# eGatewayShield.net
KiCad netlist of a schematic drawn in EAGLE
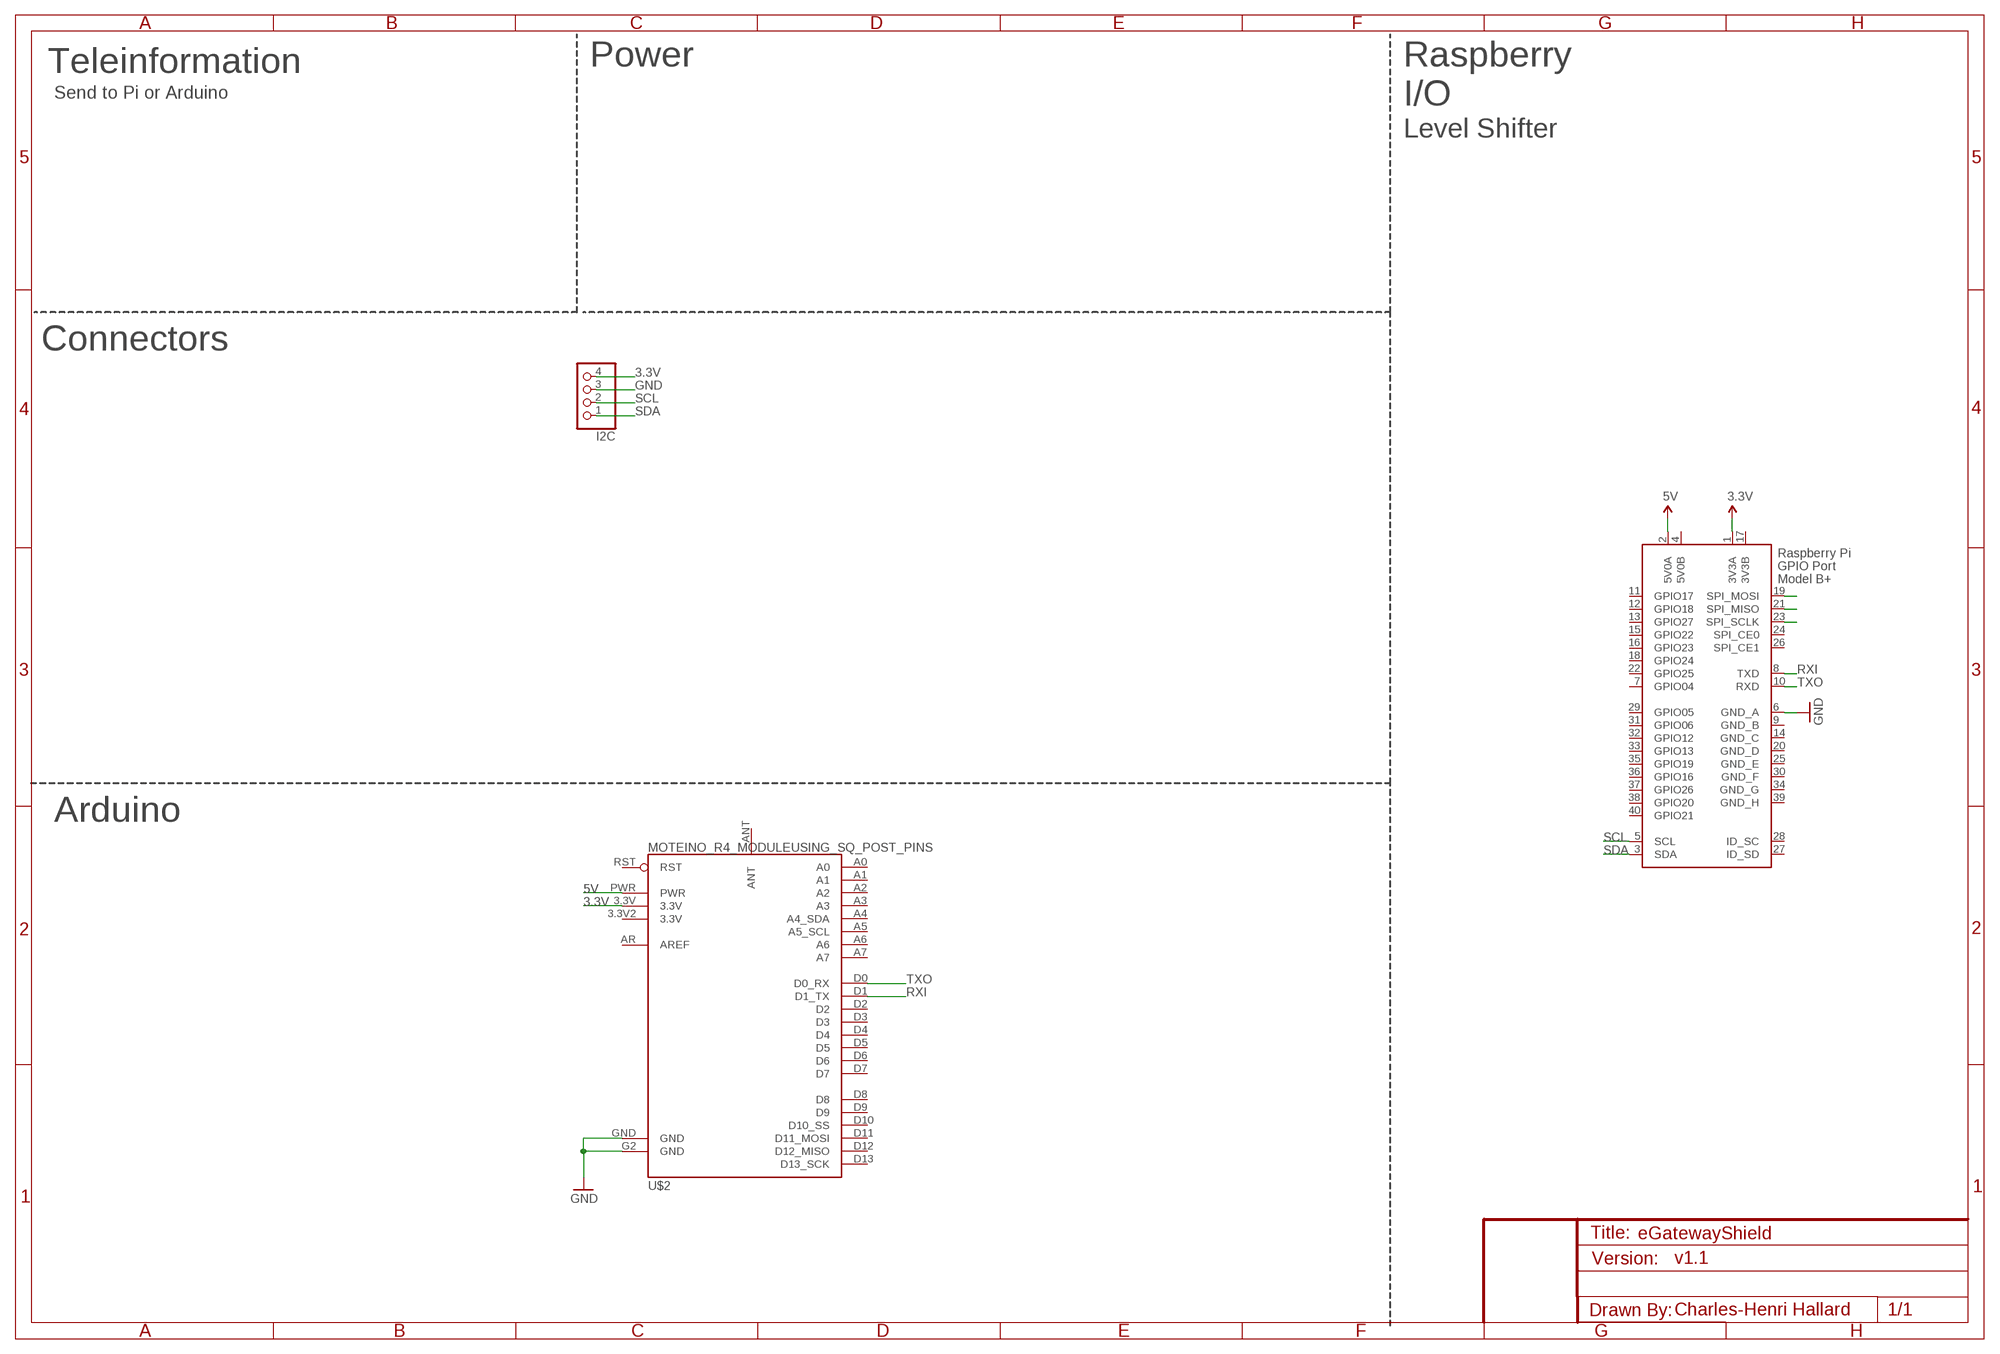
[diagram p0: schematic, sheet 1]

(export (version "E")
  (design (tool "Eeschema 10.0.6"))
  (components
    (comp (ref "I2C")
      (value "PINHD-1X4")
      (footprint "eagle-import:1X04")
      (libsource (lib "eagle-import") (part "PINHD-1X4"))
    )
    (comp (ref "U$2")
      (value "MOTEINO_R4_MODULEUSING_SQ_POST_PINS")
      (footprint "eagle-import:MOTEINTO_R4_SQ")
      (libsource (lib "eagle-import") (part "MOTEINO_R4_MODULEUSING_SQ_POST_PINS"))
    )
    (comp (ref "X1")
      (value "RASPI_BOARD_B+#_F")
      (footprint "eagle-import:RASPI_BOARD_B+_FULL")
      (libsource (lib "eagle-import") (part "RASPI_BOARD_B+#_F"))
    )
  )
  (nets
    (net (code "1") (name "/3V3B") (class "Default")
      (node (ref "X1") (pin "17") (pinfunction "3V3B_17") (pintype "power_in"))
    )
    (net (code "2") (name "/5V0B") (class "Default")
      (node (ref "X1") (pin "4") (pinfunction "5V0B_4") (pintype "power_in"))
    )
    (net (code "3") (name "/GND_B") (class "Default")
      (node (ref "X1") (pin "9") (pinfunction "GND_B_9") (pintype "power_in"))
    )
    (net (code "4") (name "/GND_C") (class "Default")
      (node (ref "X1") (pin "14") (pinfunction "GND_C_14") (pintype "power_in"))
    )
    (net (code "5") (name "/GND_D") (class "Default")
      (node (ref "X1") (pin "20") (pinfunction "GND_D_20") (pintype "power_in"))
    )
    (net (code "6") (name "/GND_E") (class "Default")
      (node (ref "X1") (pin "25") (pinfunction "GND_E_25") (pintype "power_in"))
    )
    (net (code "7") (name "/GND_F") (class "Default")
      (node (ref "X1") (pin "30") (pinfunction "GND_F_30") (pintype "power_in"))
    )
    (net (code "8") (name "/GND_G") (class "Default")
      (node (ref "X1") (pin "34") (pinfunction "GND_G_34") (pintype "power_in"))
    )
    (net (code "9") (name "/GND_H") (class "Default")
      (node (ref "X1") (pin "39") (pinfunction "GND_H_39") (pintype "power_in"))
    )
    (net (code "10") (name "/RXI") (class "Default")
      (node (ref "U$2") (pin "D1") (pinfunction "D1_TX_D1") (pintype "bidirectional"))
      (node (ref "X1") (pin "8") (pinfunction "TXD_8") (pintype "bidirectional"))
    )
    (net (code "11") (name "/SCL") (class "Default")
      (node (ref "I2C") (pin "2") (pinfunction "2_2") (pintype "passive"))
      (node (ref "X1") (pin "5") (pinfunction "SCL_5") (pintype "bidirectional"))
    )
    (net (code "12") (name "/SDA") (class "Default")
      (node (ref "I2C") (pin "1") (pinfunction "1_1") (pintype "passive"))
      (node (ref "X1") (pin "3") (pinfunction "SDA_3") (pintype "bidirectional"))
    )
    (net (code "13") (name "/TXO") (class "Default")
      (node (ref "U$2") (pin "D0") (pinfunction "D0_RX_D0") (pintype "bidirectional"))
      (node (ref "X1") (pin "10") (pinfunction "RXD_10") (pintype "bidirectional"))
    )
    (net (code "14") (name "3.3V") (class "Default")
      (node (ref "I2C") (pin "4") (pinfunction "4_4") (pintype "passive"))
      (node (ref "U$2") (pin "3.3V") (pinfunction "3.3V_3.3V") (pintype "passive"))
      (node (ref "X1") (pin "1") (pinfunction "3V3A_1") (pintype "power_in"))
    )
    (net (code "15") (name "5V") (class "Default")
      (node (ref "U$2") (pin "PWR") (pinfunction "PWR_PWR") (pintype "passive"))
      (node (ref "X1") (pin "2") (pinfunction "5V0A_2") (pintype "power_in"))
    )
    (net (code "16") (name "GND") (class "Default")
      (node (ref "I2C") (pin "3") (pinfunction "3_3") (pintype "passive"))
      (node (ref "U$2") (pin "G2") (pinfunction "GND_G2") (pintype "power_in"))
      (node (ref "U$2") (pin "GND") (pinfunction "GND_GND") (pintype "power_in"))
      (node (ref "X1") (pin "6") (pinfunction "GND_A_6") (pintype "power_in"))
    )
    (net (code "17") (name "unconnected-(U$2-3.3V-Pad3.3V2)") (class "Default")
      (node (ref "U$2") (pin "3.3V2") (pinfunction "3.3V_3.3V2") (pintype "passive"))
    )
    (net (code "18") (name "unconnected-(U$2-A4_SDA-PadA4)") (class "Default")
      (node (ref "U$2") (pin "A4") (pinfunction "A4_SDA_A4") (pintype "bidirectional"))
    )
    (net (code "19") (name "unconnected-(U$2-A5_SCL-PadA5)") (class "Default")
      (node (ref "U$2") (pin "A5") (pinfunction "A5_SCL_A5") (pintype "bidirectional"))
    )
    (net (code "20") (name "unconnected-(U$2-AREF-PadAR)") (class "Default")
      (node (ref "U$2") (pin "AR") (pinfunction "AREF_AR") (pintype "bidirectional"))
    )
    (net (code "21") (name "unconnected-(U$2-D10_SS-PadD10)") (class "Default")
      (node (ref "U$2") (pin "D10") (pinfunction "D10_SS_D10") (pintype "bidirectional"))
    )
    (net (code "22") (name "unconnected-(U$2-D11_MOSI-PadD11)") (class "Default")
      (node (ref "U$2") (pin "D11") (pinfunction "D11_MOSI_D11") (pintype "bidirectional"))
    )
    (net (code "23") (name "unconnected-(U$2-D12_MISO-PadD12)") (class "Default")
      (node (ref "U$2") (pin "D12") (pinfunction "D12_MISO_D12") (pintype "bidirectional"))
    )
    (net (code "24") (name "unconnected-(U$2-D13_SCK-PadD13)") (class "Default")
      (node (ref "U$2") (pin "D13") (pinfunction "D13_SCK_D13") (pintype "bidirectional"))
    )
    (net (code "25") (name "unconnected-(U$2-PadA0)") (class "Default")
      (node (ref "U$2") (pin "A0") (pinfunction "A0_A0") (pintype "bidirectional"))
    )
    (net (code "26") (name "unconnected-(U$2-PadA1)") (class "Default")
      (node (ref "U$2") (pin "A1") (pinfunction "A1_A1") (pintype "bidirectional"))
    )
    (net (code "27") (name "unconnected-(U$2-PadA2)") (class "Default")
      (node (ref "U$2") (pin "A2") (pinfunction "A2_A2") (pintype "bidirectional"))
    )
    (net (code "28") (name "unconnected-(U$2-PadA3)") (class "Default")
      (node (ref "U$2") (pin "A3") (pinfunction "A3_A3") (pintype "bidirectional"))
    )
    (net (code "29") (name "unconnected-(U$2-PadA6)") (class "Default")
      (node (ref "U$2") (pin "A6") (pinfunction "A6_A6") (pintype "bidirectional"))
    )
    (net (code "30") (name "unconnected-(U$2-PadA7)") (class "Default")
      (node (ref "U$2") (pin "A7") (pinfunction "A7_A7") (pintype "bidirectional"))
    )
    (net (code "31") (name "unconnected-(U$2-PadANT)") (class "Default")
      (node (ref "U$2") (pin "ANT") (pinfunction "ANT_ANT") (pintype "passive"))
    )
    (net (code "32") (name "unconnected-(U$2-PadD2)") (class "Default")
      (node (ref "U$2") (pin "D2") (pinfunction "D2_D2") (pintype "bidirectional"))
    )
    (net (code "33") (name "unconnected-(U$2-PadD3)") (class "Default")
      (node (ref "U$2") (pin "D3") (pinfunction "D3_D3") (pintype "bidirectional"))
    )
    (net (code "34") (name "unconnected-(U$2-PadD4)") (class "Default")
      (node (ref "U$2") (pin "D4") (pinfunction "D4_D4") (pintype "bidirectional"))
    )
    (net (code "35") (name "unconnected-(U$2-PadD5)") (class "Default")
      (node (ref "U$2") (pin "D5") (pinfunction "D5_D5") (pintype "bidirectional"))
    )
    (net (code "36") (name "unconnected-(U$2-PadD6)") (class "Default")
      (node (ref "U$2") (pin "D6") (pinfunction "D6_D6") (pintype "bidirectional"))
    )
    (net (code "37") (name "unconnected-(U$2-PadD7)") (class "Default")
      (node (ref "U$2") (pin "D7") (pinfunction "D7_D7") (pintype "bidirectional"))
    )
    (net (code "38") (name "unconnected-(U$2-PadD8)") (class "Default")
      (node (ref "U$2") (pin "D8") (pinfunction "D8_D8") (pintype "bidirectional"))
    )
    (net (code "39") (name "unconnected-(U$2-PadD9)") (class "Default")
      (node (ref "U$2") (pin "D9") (pinfunction "D9_D9") (pintype "bidirectional"))
    )
    (net (code "40") (name "unconnected-(U$2-PadRST)") (class "Default")
      (node (ref "U$2") (pin "RST") (pinfunction "RST_RST") (pintype "bidirectional"))
    )
    (net (code "41") (name "unconnected-(X1-GPIO04-Pad7)") (class "Default")
      (node (ref "X1") (pin "7") (pinfunction "GPIO04_7") (pintype "bidirectional"))
    )
    (net (code "42") (name "unconnected-(X1-GPIO05-Pad29)") (class "Default")
      (node (ref "X1") (pin "29") (pinfunction "GPIO05_29") (pintype "no_connect"))
    )
    (net (code "43") (name "unconnected-(X1-GPIO06-Pad31)") (class "Default")
      (node (ref "X1") (pin "31") (pinfunction "GPIO06_31") (pintype "no_connect"))
    )
    (net (code "44") (name "unconnected-(X1-GPIO12-Pad32)") (class "Default")
      (node (ref "X1") (pin "32") (pinfunction "GPIO12_32") (pintype "no_connect"))
    )
    (net (code "45") (name "unconnected-(X1-GPIO13-Pad33)") (class "Default")
      (node (ref "X1") (pin "33") (pinfunction "GPIO13_33") (pintype "no_connect"))
    )
    (net (code "46") (name "unconnected-(X1-GPIO16-Pad36)") (class "Default")
      (node (ref "X1") (pin "36") (pinfunction "GPIO16_36") (pintype "no_connect"))
    )
    (net (code "47") (name "unconnected-(X1-GPIO17-Pad11)") (class "Default")
      (node (ref "X1") (pin "11") (pinfunction "GPIO17_11") (pintype "bidirectional"))
    )
    (net (code "48") (name "unconnected-(X1-GPIO18-Pad12)") (class "Default")
      (node (ref "X1") (pin "12") (pinfunction "GPIO18_12") (pintype "bidirectional"))
    )
    (net (code "49") (name "unconnected-(X1-GPIO19-Pad35)") (class "Default")
      (node (ref "X1") (pin "35") (pinfunction "GPIO19_35") (pintype "no_connect"))
    )
    (net (code "50") (name "unconnected-(X1-GPIO20-Pad38)") (class "Default")
      (node (ref "X1") (pin "38") (pinfunction "GPIO20_38") (pintype "no_connect"))
    )
    (net (code "51") (name "unconnected-(X1-GPIO21-Pad40)") (class "Default")
      (node (ref "X1") (pin "40") (pinfunction "GPIO21_40") (pintype "no_connect"))
    )
    (net (code "52") (name "unconnected-(X1-GPIO22-Pad15)") (class "Default")
      (node (ref "X1") (pin "15") (pinfunction "GPIO22_15") (pintype "bidirectional"))
    )
    (net (code "53") (name "unconnected-(X1-GPIO23-Pad16)") (class "Default")
      (node (ref "X1") (pin "16") (pinfunction "GPIO23_16") (pintype "bidirectional"))
    )
    (net (code "54") (name "unconnected-(X1-GPIO24-Pad18)") (class "Default")
      (node (ref "X1") (pin "18") (pinfunction "GPIO24_18") (pintype "bidirectional"))
    )
    (net (code "55") (name "unconnected-(X1-GPIO25-Pad22)") (class "Default")
      (node (ref "X1") (pin "22") (pinfunction "GPIO25_22") (pintype "bidirectional"))
    )
    (net (code "56") (name "unconnected-(X1-GPIO26-Pad37)") (class "Default")
      (node (ref "X1") (pin "37") (pinfunction "GPIO26_37") (pintype "no_connect"))
    )
    (net (code "57") (name "unconnected-(X1-GPIO27-Pad13)") (class "Default")
      (node (ref "X1") (pin "13") (pinfunction "GPIO27_13") (pintype "bidirectional"))
    )
    (net (code "58") (name "unconnected-(X1-ID_SC-Pad28)") (class "Default")
      (node (ref "X1") (pin "28") (pinfunction "ID_SC_28") (pintype "no_connect"))
    )
    (net (code "59") (name "unconnected-(X1-ID_SD-Pad27)") (class "Default")
      (node (ref "X1") (pin "27") (pinfunction "ID_SD_27") (pintype "no_connect"))
    )
    (net (code "60") (name "unconnected-(X1-SPI_CE0-Pad24)") (class "Default")
      (node (ref "X1") (pin "24") (pinfunction "SPI_CE0_24") (pintype "bidirectional"))
    )
    (net (code "61") (name "unconnected-(X1-SPI_CE1-Pad26)") (class "Default")
      (node (ref "X1") (pin "26") (pinfunction "SPI_CE1_26") (pintype "bidirectional"))
    )
    (net (code "62") (name "unconnected-(X1-SPI_MISO-Pad21)") (class "Default")
      (node (ref "X1") (pin "21") (pinfunction "SPI_MISO_21") (pintype "bidirectional"))
    )
    (net (code "63") (name "unconnected-(X1-SPI_MOSI-Pad19)") (class "Default")
      (node (ref "X1") (pin "19") (pinfunction "SPI_MOSI_19") (pintype "bidirectional"))
    )
    (net (code "64") (name "unconnected-(X1-SPI_SCLK-Pad23)") (class "Default")
      (node (ref "X1") (pin "23") (pinfunction "SPI_SCLK_23") (pintype "bidirectional"))
    )
  )
)
